# hermes.net
KiCad netlist of a schematic drawn in EAGLE
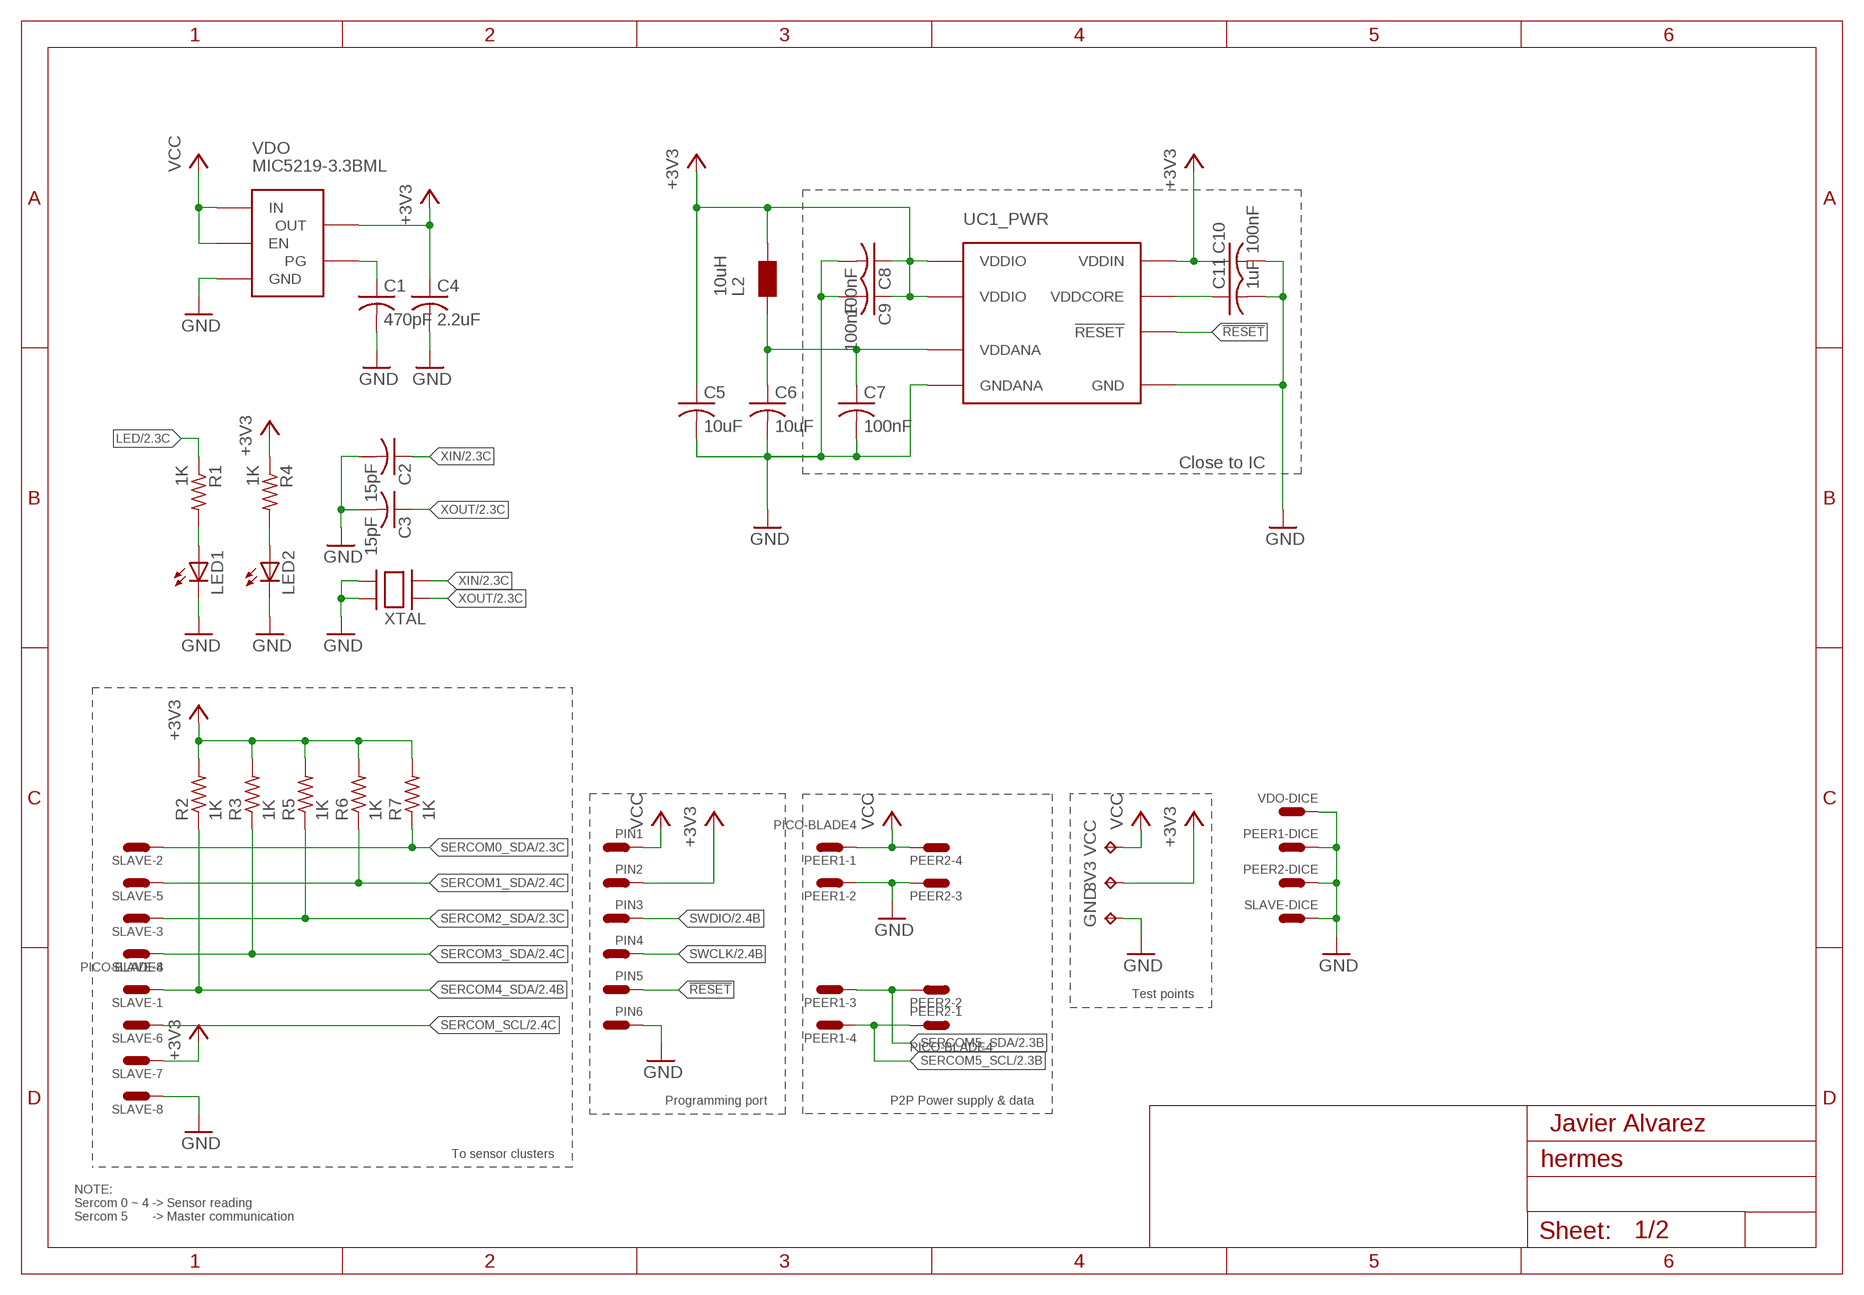
[diagram p0: schematic, sheet 1]
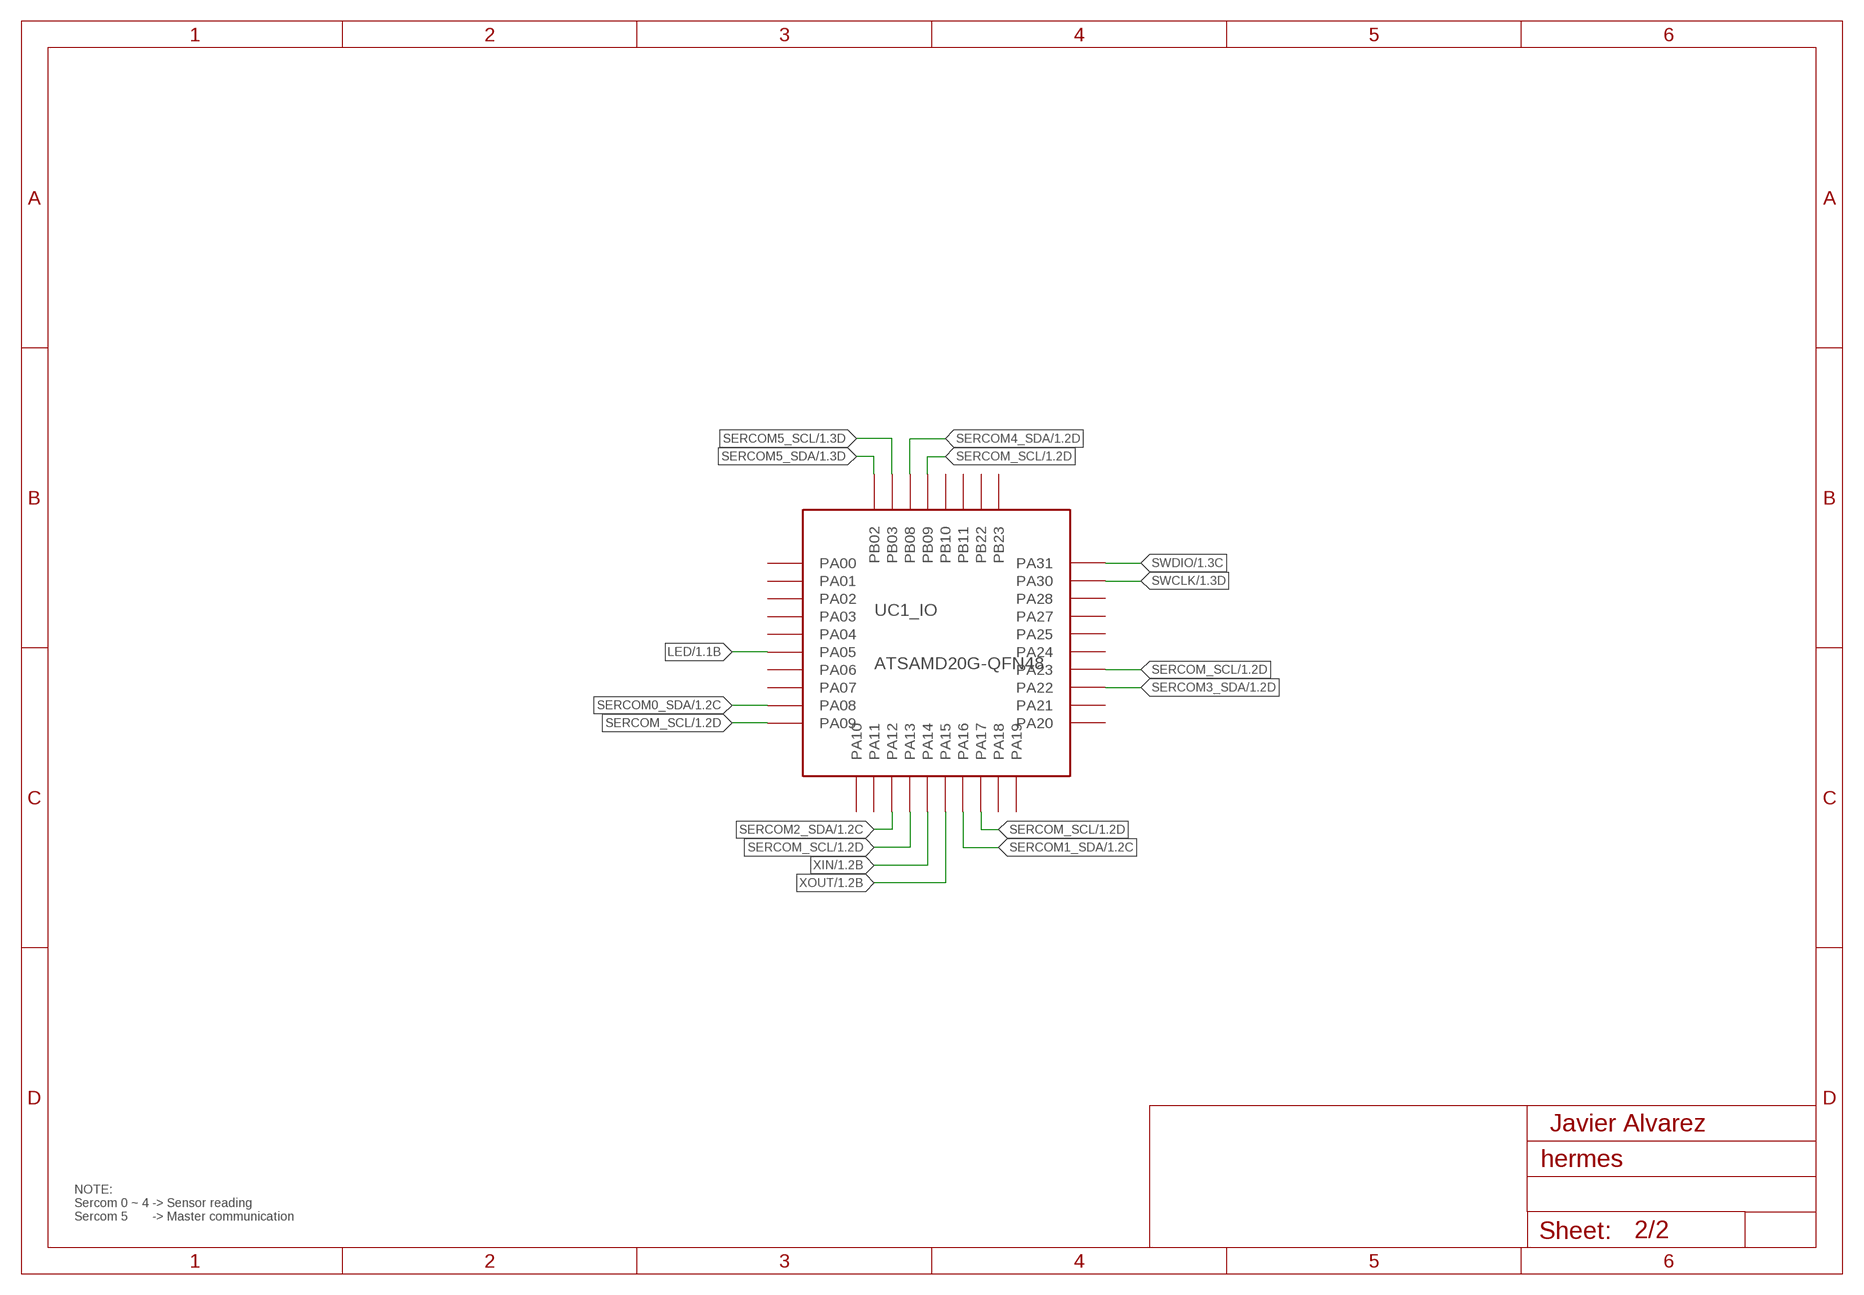
[diagram p1: schematic, sheet 2]

(export (version "E")
  (design (tool "Eeschema 10.0.6"))
  (components
    (comp (ref "UC1")
      (value "ATSAMD20G-QFN48")
      (footprint "eagle-import:QFN-48")
      (libsource (lib "eagle-import") (part "ATSAMD20G-QFN48"))
    )
    (comp (ref "3V3")
      (value "TPB1,27")
      (footprint "eagle-import:B1,27")
      (libsource (lib "eagle-import") (part "TPB1,27"))
    )
    (comp (ref "C1")
      (value "470pF")
      (footprint "eagle-import:C0201")
      (libsource (lib "eagle-import") (part "C-USC0201"))
    )
    (comp (ref "C2")
      (value "15pF")
      (footprint "eagle-import:C0201")
      (libsource (lib "eagle-import") (part "C-USC0201"))
    )
    (comp (ref "C3")
      (value "15pF")
      (footprint "eagle-import:C0201")
      (libsource (lib "eagle-import") (part "C-USC0201"))
    )
    (comp (ref "C4")
      (value "2.2uF")
      (footprint "eagle-import:C0201")
      (libsource (lib "eagle-import") (part "C-USC0201"))
    )
    (comp (ref "C5")
      (value "10uF")
      (footprint "eagle-import:C0402")
      (libsource (lib "eagle-import") (part "C-USC0402"))
    )
    (comp (ref "C6")
      (value "10uF")
      (footprint "eagle-import:C0402")
      (libsource (lib "eagle-import") (part "C-USC0402"))
    )
    (comp (ref "C7")
      (value "100nF")
      (footprint "eagle-import:C0201")
      (libsource (lib "eagle-import") (part "C-USC0201"))
    )
    (comp (ref "C8")
      (value "100nF")
      (footprint "eagle-import:C0201")
      (libsource (lib "eagle-import") (part "C-USC0201"))
    )
    (comp (ref "C9")
      (value "100nF")
      (footprint "eagle-import:C0201")
      (libsource (lib "eagle-import") (part "C-USC0201"))
    )
    (comp (ref "C10")
      (value "100nF")
      (footprint "eagle-import:C0201")
      (libsource (lib "eagle-import") (part "C-USC0201"))
    )
    (comp (ref "C11")
      (value "1uF")
      (footprint "eagle-import:C0201")
      (libsource (lib "eagle-import") (part "C-USC0201"))
    )
    (comp (ref "GND")
      (value "TPB1,27")
      (footprint "eagle-import:B1,27")
      (libsource (lib "eagle-import") (part "TPB1,27"))
    )
    (comp (ref "L2")
      (value "10uH")
      (footprint "eagle-import:L2215")
      (libsource (lib "eagle-import") (part "SPM5030-HZ"))
    )
    (comp (ref "LED1")
      (value "LED_ESML0603")
      (footprint "eagle-import:LED_SML0603")
      (libsource (lib "eagle-import") (part "LED_ESML0603"))
    )
    (comp (ref "LED2")
      (value "LED_ESML0603")
      (footprint "eagle-import:LED_SML0603")
      (libsource (lib "eagle-import") (part "LED_ESML0603"))
    )
    (comp (ref "PEER1")
      (value "PICO-BLADE4")
      (footprint "eagle-import:PICO-BLADE4")
      (libsource (lib "eagle-import") (part "PICO-BLADE4"))
    )
    (comp (ref "PEER2")
      (value "PICO-BLADE4")
      (footprint "eagle-import:PICO-BLADE4")
      (libsource (lib "eagle-import") (part "PICO-BLADE4"))
    )
    (comp (ref "PIN1")
      (value "SINGLE-PIN")
      (footprint "eagle-import:PAD5025")
      (libsource (lib "eagle-import") (part "SINGLE-PIN"))
    )
    (comp (ref "PIN2")
      (value "SINGLE-PIN")
      (footprint "eagle-import:PAD5025")
      (libsource (lib "eagle-import") (part "SINGLE-PIN"))
    )
    (comp (ref "PIN3")
      (value "SINGLE-PIN")
      (footprint "eagle-import:PAD5025")
      (libsource (lib "eagle-import") (part "SINGLE-PIN"))
    )
    (comp (ref "PIN4")
      (value "SINGLE-PIN")
      (footprint "eagle-import:PAD5025")
      (libsource (lib "eagle-import") (part "SINGLE-PIN"))
    )
    (comp (ref "PIN5")
      (value "SINGLE-PIN")
      (footprint "eagle-import:PAD5025")
      (libsource (lib "eagle-import") (part "SINGLE-PIN"))
    )
    (comp (ref "PIN6")
      (value "SINGLE-PIN")
      (footprint "eagle-import:PAD5025")
      (libsource (lib "eagle-import") (part "SINGLE-PIN"))
    )
    (comp (ref "R1")
      (value "1K")
      (footprint "eagle-import:R0201")
      (libsource (lib "eagle-import") (part "R-US_R0201"))
    )
    (comp (ref "R2")
      (value "1K")
      (footprint "eagle-import:R0201")
      (libsource (lib "eagle-import") (part "R-US_R0201"))
    )
    (comp (ref "R3")
      (value "1K")
      (footprint "eagle-import:R0201")
      (libsource (lib "eagle-import") (part "R-US_R0201"))
    )
    (comp (ref "R4")
      (value "1K")
      (footprint "eagle-import:R0201")
      (libsource (lib "eagle-import") (part "R-US_R0201"))
    )
    (comp (ref "R5")
      (value "1K")
      (footprint "eagle-import:R0201")
      (libsource (lib "eagle-import") (part "R-US_R0201"))
    )
    (comp (ref "R6")
      (value "1K")
      (footprint "eagle-import:R0201")
      (libsource (lib "eagle-import") (part "R-US_R0201"))
    )
    (comp (ref "R7")
      (value "1K")
      (footprint "eagle-import:R0201")
      (libsource (lib "eagle-import") (part "R-US_R0201"))
    )
    (comp (ref "SLAVE")
      (value "PICO-BLADE8")
      (footprint "eagle-import:PICO-BLADE8")
      (libsource (lib "eagle-import") (part "PICO-BLADE8"))
    )
    (comp (ref "VCC")
      (value "TPB1,27")
      (footprint "eagle-import:B1,27")
      (libsource (lib "eagle-import") (part "TPB1,27"))
    )
    (comp (ref "VDO")
      (value "MIC5219-3.3BML")
      (footprint "eagle-import:MLF-6")
      (libsource (lib "eagle-import") (part "MIC5219-3.3BML"))
    )
    (comp (ref "XTAL")
      (value "LFXTAL059596CUTT")
      (footprint "eagle-import:2X1.6")
      (libsource (lib "eagle-import") (part "LFXTAL059596CUTT"))
    )
  )
  (nets
    (net (code "1") (name "+3V3") (class "Default")
      (node (ref "3V3") (pin "TP") (pinfunction "TP_TP") (pintype "input"))
      (node (ref "C10") (pin "1") (pinfunction "1_1") (pintype "passive"))
      (node (ref "C4") (pin "1") (pinfunction "1_1") (pintype "passive"))
      (node (ref "C5") (pin "1") (pinfunction "1_1") (pintype "passive"))
      (node (ref "C8") (pin "1") (pinfunction "1_1") (pintype "passive"))
      (node (ref "C9") (pin "1") (pinfunction "1_1") (pintype "passive"))
      (node (ref "L2") (pin "P$2") (pinfunction "P$2_P$2") (pintype "bidirectional"))
      (node (ref "PIN2") (pin "P$1") (pinfunction "P$1_P$1") (pintype "bidirectional"))
      (node (ref "R2") (pin "2") (pinfunction "2_2") (pintype "passive"))
      (node (ref "R3") (pin "2") (pinfunction "2_2") (pintype "passive"))
      (node (ref "R4") (pin "1") (pinfunction "1_1") (pintype "passive"))
      (node (ref "R5") (pin "2") (pinfunction "2_2") (pintype "passive"))
      (node (ref "R6") (pin "2") (pinfunction "2_2") (pintype "passive"))
      (node (ref "R7") (pin "2") (pinfunction "2_2") (pintype "passive"))
      (node (ref "SLAVE") (pin "P$9") (pinfunction "P$1_P$9") (pintype "bidirectional"))
      (node (ref "UC1") (pin "P$17") (pinfunction "VDDIO_P$17") (pintype "bidirectional"))
      (node (ref "UC1") (pin "P$36") (pinfunction "VDDIO_P$36") (pintype "bidirectional"))
      (node (ref "UC1") (pin "P$44") (pinfunction "VDDIN_P$44") (pintype "bidirectional"))
      (node (ref "VDO") (pin "P$4") (pinfunction "OUT_P$4") (pintype "bidirectional"))
    )
    (net (code "2") (name "GND") (class "Default")
      (node (ref "C1") (pin "2") (pinfunction "2_2") (pintype "passive"))
      (node (ref "C10") (pin "2") (pinfunction "2_2") (pintype "passive"))
      (node (ref "C11") (pin "2") (pinfunction "2_2") (pintype "passive"))
      (node (ref "C2") (pin "2") (pinfunction "2_2") (pintype "passive"))
      (node (ref "C3") (pin "2") (pinfunction "2_2") (pintype "passive"))
      (node (ref "C4") (pin "2") (pinfunction "2_2") (pintype "passive"))
      (node (ref "C5") (pin "2") (pinfunction "2_2") (pintype "passive"))
      (node (ref "C6") (pin "2") (pinfunction "2_2") (pintype "passive"))
      (node (ref "C7") (pin "2") (pinfunction "2_2") (pintype "passive"))
      (node (ref "C8") (pin "2") (pinfunction "2_2") (pintype "passive"))
      (node (ref "C9") (pin "2") (pinfunction "2_2") (pintype "passive"))
      (node (ref "GND") (pin "TP") (pinfunction "TP_TP") (pintype "input"))
      (node (ref "LED1") (pin "C") (pinfunction "C_C") (pintype "passive"))
      (node (ref "LED2") (pin "C") (pinfunction "C_C") (pintype "passive"))
      (node (ref "PEER1") (pin "P$1") (pinfunction "P$1_P$1") (pintype "bidirectional"))
      (node (ref "PEER1") (pin "P$2") (pinfunction "P$1_P$2") (pintype "bidirectional"))
      (node (ref "PEER1") (pin "P$4") (pinfunction "P$1_P$4") (pintype "bidirectional"))
      (node (ref "PEER2") (pin "P$1") (pinfunction "P$1_P$1") (pintype "bidirectional"))
      (node (ref "PEER2") (pin "P$2") (pinfunction "P$1_P$2") (pintype "bidirectional"))
      (node (ref "PEER2") (pin "P$5") (pinfunction "P$1_P$5") (pintype "bidirectional"))
      (node (ref "PIN6") (pin "P$1") (pinfunction "P$1_P$1") (pintype "bidirectional"))
      (node (ref "SLAVE") (pin "P$1") (pinfunction "P$1_P$1") (pintype "bidirectional"))
      (node (ref "SLAVE") (pin "P$10") (pinfunction "P$1_P$10") (pintype "bidirectional"))
      (node (ref "SLAVE") (pin "P$2") (pinfunction "P$1_P$2") (pintype "bidirectional"))
      (node (ref "UC1") (pin "P$18") (pinfunction "GND_P$18") (pintype "bidirectional"))
      (node (ref "UC1") (pin "P$35") (pinfunction "GND_P$35") (pintype "bidirectional"))
      (node (ref "UC1") (pin "P$42") (pinfunction "GND_P$42") (pintype "bidirectional"))
      (node (ref "UC1") (pin "P$49") (pinfunction "GND_P$49") (pintype "bidirectional"))
      (node (ref "UC1") (pin "P$5") (pinfunction "GNDANA_P$5") (pintype "bidirectional"))
      (node (ref "VDO") (pin "P$2") (pinfunction "GND_P$2") (pintype "bidirectional"))
      (node (ref "VDO") (pin "P$7") (pinfunction "P$1_P$7") (pintype "bidirectional"))
      (node (ref "XTAL") (pin "GND@1") (pinfunction "GND_GND@1") (pintype "bidirectional"))
      (node (ref "XTAL") (pin "GND@2") (pinfunction "GND_GND@2") (pintype "bidirectional"))
    )
    (net (code "3") (name "LED") (class "Default")
      (node (ref "R1") (pin "1") (pinfunction "1_1") (pintype "passive"))
      (node (ref "UC1") (pin "P$10") (pinfunction "PA05_P$10") (pintype "bidirectional"))
    )
    (net (code "4") (name "Net-(LED1-PadA)") (class "Default")
      (node (ref "LED1") (pin "A") (pinfunction "A_A") (pintype "passive"))
      (node (ref "R1") (pin "2") (pinfunction "2_2") (pintype "passive"))
    )
    (net (code "5") (name "Net-(LED2-PadA)") (class "Default")
      (node (ref "LED2") (pin "A") (pinfunction "A_A") (pintype "passive"))
      (node (ref "R4") (pin "2") (pinfunction "2_2") (pintype "passive"))
    )
    (net (code "6") (name "Net-(UC1B-VDDANA)") (class "Default")
      (node (ref "C6") (pin "1") (pinfunction "1_1") (pintype "passive"))
      (node (ref "C7") (pin "1") (pinfunction "1_1") (pintype "passive"))
      (node (ref "L2") (pin "P$1") (pinfunction "P$1_P$1") (pintype "bidirectional"))
      (node (ref "UC1") (pin "P$6") (pinfunction "VDDANA_P$6") (pintype "bidirectional"))
    )
    (net (code "7") (name "Net-(UC1B-VDDCORE)") (class "Default")
      (node (ref "C11") (pin "1") (pinfunction "1_1") (pintype "passive"))
      (node (ref "UC1") (pin "P$43") (pinfunction "VDDCORE_P$43") (pintype "bidirectional"))
    )
    (net (code "8") (name "Net-(VDOB-PG)") (class "Default")
      (node (ref "C1") (pin "1") (pinfunction "1_1") (pintype "passive"))
      (node (ref "VDO") (pin "P$6") (pinfunction "PG_P$6") (pintype "bidirectional"))
    )
    (net (code "9") (name "SERCOM0_SDA") (class "Default")
      (node (ref "R7") (pin "1") (pinfunction "1_1") (pintype "passive"))
      (node (ref "SLAVE") (pin "P$4") (pinfunction "P$1_P$4") (pintype "bidirectional"))
      (node (ref "UC1") (pin "P$13") (pinfunction "PA08_P$13") (pintype "bidirectional"))
    )
    (net (code "10") (name "SERCOM1_SDA") (class "Default")
      (node (ref "R6") (pin "1") (pinfunction "1_1") (pintype "passive"))
      (node (ref "SLAVE") (pin "P$7") (pinfunction "P$1_P$7") (pintype "bidirectional"))
      (node (ref "UC1") (pin "P$25") (pinfunction "PA16_P$25") (pintype "bidirectional"))
    )
    (net (code "11") (name "SERCOM2_SDA") (class "Default")
      (node (ref "R5") (pin "1") (pinfunction "1_1") (pintype "passive"))
      (node (ref "SLAVE") (pin "P$5") (pinfunction "P$1_P$5") (pintype "bidirectional"))
      (node (ref "UC1") (pin "P$21") (pinfunction "PA12_P$21") (pintype "bidirectional"))
    )
    (net (code "12") (name "SERCOM3_SDA") (class "Default")
      (node (ref "R3") (pin "1") (pinfunction "1_1") (pintype "passive"))
      (node (ref "SLAVE") (pin "P$6") (pinfunction "P$1_P$6") (pintype "bidirectional"))
      (node (ref "UC1") (pin "P$31") (pinfunction "PA22_P$31") (pintype "bidirectional"))
    )
    (net (code "13") (name "SERCOM4_SDA") (class "Default")
      (node (ref "R2") (pin "1") (pinfunction "1_1") (pintype "passive"))
      (node (ref "SLAVE") (pin "P$3") (pinfunction "P$1_P$3") (pintype "passive"))
      (node (ref "UC1") (pin "P$7") (pinfunction "PB08_P$7") (pintype "bidirectional"))
    )
    (net (code "14") (name "SERCOM5_SCL") (class "Default")
      (node (ref "PEER1") (pin "P$6") (pinfunction "P$1_P$6") (pintype "bidirectional"))
      (node (ref "PEER2") (pin "P$3") (pinfunction "P$1_P$3") (pintype "passive"))
      (node (ref "UC1") (pin "P$48") (pinfunction "PB03_P$48") (pintype "bidirectional"))
    )
    (net (code "15") (name "SERCOM5_SDA") (class "Default")
      (node (ref "PEER1") (pin "P$5") (pinfunction "P$1_P$5") (pintype "bidirectional"))
      (node (ref "PEER2") (pin "P$4") (pinfunction "P$1_P$4") (pintype "bidirectional"))
      (node (ref "UC1") (pin "P$47") (pinfunction "PB02_P$47") (pintype "bidirectional"))
    )
    (net (code "16") (name "SERCOM_SCL") (class "Default")
      (node (ref "SLAVE") (pin "P$8") (pinfunction "P$1_P$8") (pintype "bidirectional"))
      (node (ref "UC1") (pin "P$14") (pinfunction "PA09_P$14") (pintype "bidirectional"))
      (node (ref "UC1") (pin "P$22") (pinfunction "PA13_P$22") (pintype "bidirectional"))
      (node (ref "UC1") (pin "P$26") (pinfunction "PA17_P$26") (pintype "bidirectional"))
      (node (ref "UC1") (pin "P$32") (pinfunction "PA23_P$32") (pintype "bidirectional"))
      (node (ref "UC1") (pin "P$8") (pinfunction "PB09_P$8") (pintype "bidirectional"))
    )
    (net (code "17") (name "SWCLK") (class "Default")
      (node (ref "PIN4") (pin "P$1") (pinfunction "P$1_P$1") (pintype "bidirectional"))
      (node (ref "UC1") (pin "P$45") (pinfunction "PA30_P$45") (pintype "bidirectional"))
    )
    (net (code "18") (name "SWDIO") (class "Default")
      (node (ref "PIN3") (pin "P$1") (pinfunction "P$1_P$1") (pintype "bidirectional"))
      (node (ref "UC1") (pin "P$46") (pinfunction "PA31_P$46") (pintype "bidirectional"))
    )
    (net (code "19") (name "VCC") (class "Default")
      (node (ref "PEER1") (pin "P$3") (pinfunction "P$1_P$3") (pintype "passive"))
      (node (ref "PEER2") (pin "P$6") (pinfunction "P$1_P$6") (pintype "bidirectional"))
      (node (ref "PIN1") (pin "P$1") (pinfunction "P$1_P$1") (pintype "bidirectional"))
      (node (ref "VCC") (pin "TP") (pinfunction "TP_TP") (pintype "input"))
      (node (ref "VDO") (pin "P$1") (pinfunction "EN_P$1") (pintype "bidirectional"))
      (node (ref "VDO") (pin "P$3") (pinfunction "IN_P$3") (pintype "bidirectional"))
    )
    (net (code "20") (name "XIN") (class "Default")
      (node (ref "C2") (pin "1") (pinfunction "1_1") (pintype "passive"))
      (node (ref "UC1") (pin "P$23") (pinfunction "PA14_P$23") (pintype "bidirectional"))
      (node (ref "XTAL") (pin "XTAL@1") (pinfunction "XTAL_XTAL@1") (pintype "bidirectional"))
    )
    (net (code "21") (name "XOUT") (class "Default")
      (node (ref "C3") (pin "1") (pinfunction "1_1") (pintype "passive"))
      (node (ref "UC1") (pin "P$24") (pinfunction "PA15_P$24") (pintype "bidirectional"))
      (node (ref "XTAL") (pin "XTAL@2") (pinfunction "XTAL_XTAL@2") (pintype "bidirectional"))
    )
    (net (code "22") (name "unconnected-(UC1A-PA00-PadP$1)") (class "Default")
      (node (ref "UC1") (pin "P$1") (pinfunction "PA00_P$1") (pintype "bidirectional"))
    )
    (net (code "23") (name "unconnected-(UC1A-PA01-PadP$2)") (class "Default")
      (node (ref "UC1") (pin "P$2") (pinfunction "PA01_P$2") (pintype "bidirectional"))
    )
    (net (code "24") (name "unconnected-(UC1A-PA02-PadP$3)") (class "Default")
      (node (ref "UC1") (pin "P$3") (pinfunction "PA02_P$3") (pintype "bidirectional"))
    )
    (net (code "25") (name "unconnected-(UC1A-PA03-PadP$4)") (class "Default")
      (node (ref "UC1") (pin "P$4") (pinfunction "PA03_P$4") (pintype "bidirectional"))
    )
    (net (code "26") (name "unconnected-(UC1A-PA04-PadP$9)") (class "Default")
      (node (ref "UC1") (pin "P$9") (pinfunction "PA04_P$9") (pintype "bidirectional"))
    )
    (net (code "27") (name "unconnected-(UC1A-PA06-PadP$11)") (class "Default")
      (node (ref "UC1") (pin "P$11") (pinfunction "PA06_P$11") (pintype "bidirectional"))
    )
    (net (code "28") (name "unconnected-(UC1A-PA07-PadP$12)") (class "Default")
      (node (ref "UC1") (pin "P$12") (pinfunction "PA07_P$12") (pintype "bidirectional"))
    )
    (net (code "29") (name "unconnected-(UC1A-PA10-PadP$15)") (class "Default")
      (node (ref "UC1") (pin "P$15") (pinfunction "PA10_P$15") (pintype "bidirectional"))
    )
    (net (code "30") (name "unconnected-(UC1A-PA11-PadP$16)") (class "Default")
      (node (ref "UC1") (pin "P$16") (pinfunction "PA11_P$16") (pintype "bidirectional"))
    )
    (net (code "31") (name "unconnected-(UC1A-PA18-PadP$27)") (class "Default")
      (node (ref "UC1") (pin "P$27") (pinfunction "PA18_P$27") (pintype "bidirectional"))
    )
    (net (code "32") (name "unconnected-(UC1A-PA19-PadP$28)") (class "Default")
      (node (ref "UC1") (pin "P$28") (pinfunction "PA19_P$28") (pintype "bidirectional"))
    )
    (net (code "33") (name "unconnected-(UC1A-PA20-PadP$29)") (class "Default")
      (node (ref "UC1") (pin "P$29") (pinfunction "PA20_P$29") (pintype "bidirectional"))
    )
    (net (code "34") (name "unconnected-(UC1A-PA21-PadP$30)") (class "Default")
      (node (ref "UC1") (pin "P$30") (pinfunction "PA21_P$30") (pintype "bidirectional"))
    )
    (net (code "35") (name "unconnected-(UC1A-PA24-PadP$33)") (class "Default")
      (node (ref "UC1") (pin "P$33") (pinfunction "PA24_P$33") (pintype "bidirectional"))
    )
    (net (code "36") (name "unconnected-(UC1A-PA25-PadP$34)") (class "Default")
      (node (ref "UC1") (pin "P$34") (pinfunction "PA25_P$34") (pintype "bidirectional"))
    )
    (net (code "37") (name "unconnected-(UC1A-PA27-PadP$39)") (class "Default")
      (node (ref "UC1") (pin "P$39") (pinfunction "PA27_P$39") (pintype "bidirectional"))
    )
    (net (code "38") (name "unconnected-(UC1A-PA28-PadP$41)") (class "Default")
      (node (ref "UC1") (pin "P$41") (pinfunction "PA28_P$41") (pintype "bidirectional"))
    )
    (net (code "39") (name "unconnected-(UC1A-PB10-PadP$19)") (class "Default")
      (node (ref "UC1") (pin "P$19") (pinfunction "PB10_P$19") (pintype "bidirectional"))
    )
    (net (code "40") (name "unconnected-(UC1A-PB11-PadP$20)") (class "Default")
      (node (ref "UC1") (pin "P$20") (pinfunction "PB11_P$20") (pintype "bidirectional"))
    )
    (net (code "41") (name "unconnected-(UC1A-PB22-PadP$37)") (class "Default")
      (node (ref "UC1") (pin "P$37") (pinfunction "PB22_P$37") (pintype "bidirectional"))
    )
    (net (code "42") (name "unconnected-(UC1A-PB23-PadP$38)") (class "Default")
      (node (ref "UC1") (pin "P$38") (pinfunction "PB23_P$38") (pintype "bidirectional"))
    )
    (net (code "43") (name "~{RESET}") (class "Default")
      (node (ref "PIN5") (pin "P$1") (pinfunction "P$1_P$1") (pintype "bidirectional"))
      (node (ref "UC1") (pin "P$40") (pinfunction "~{RESET}_P$40") (pintype "bidirectional"))
    )
  )
)
